# Radio_USB.net
KiCad netlist of a schematic drawn in Altium Designer
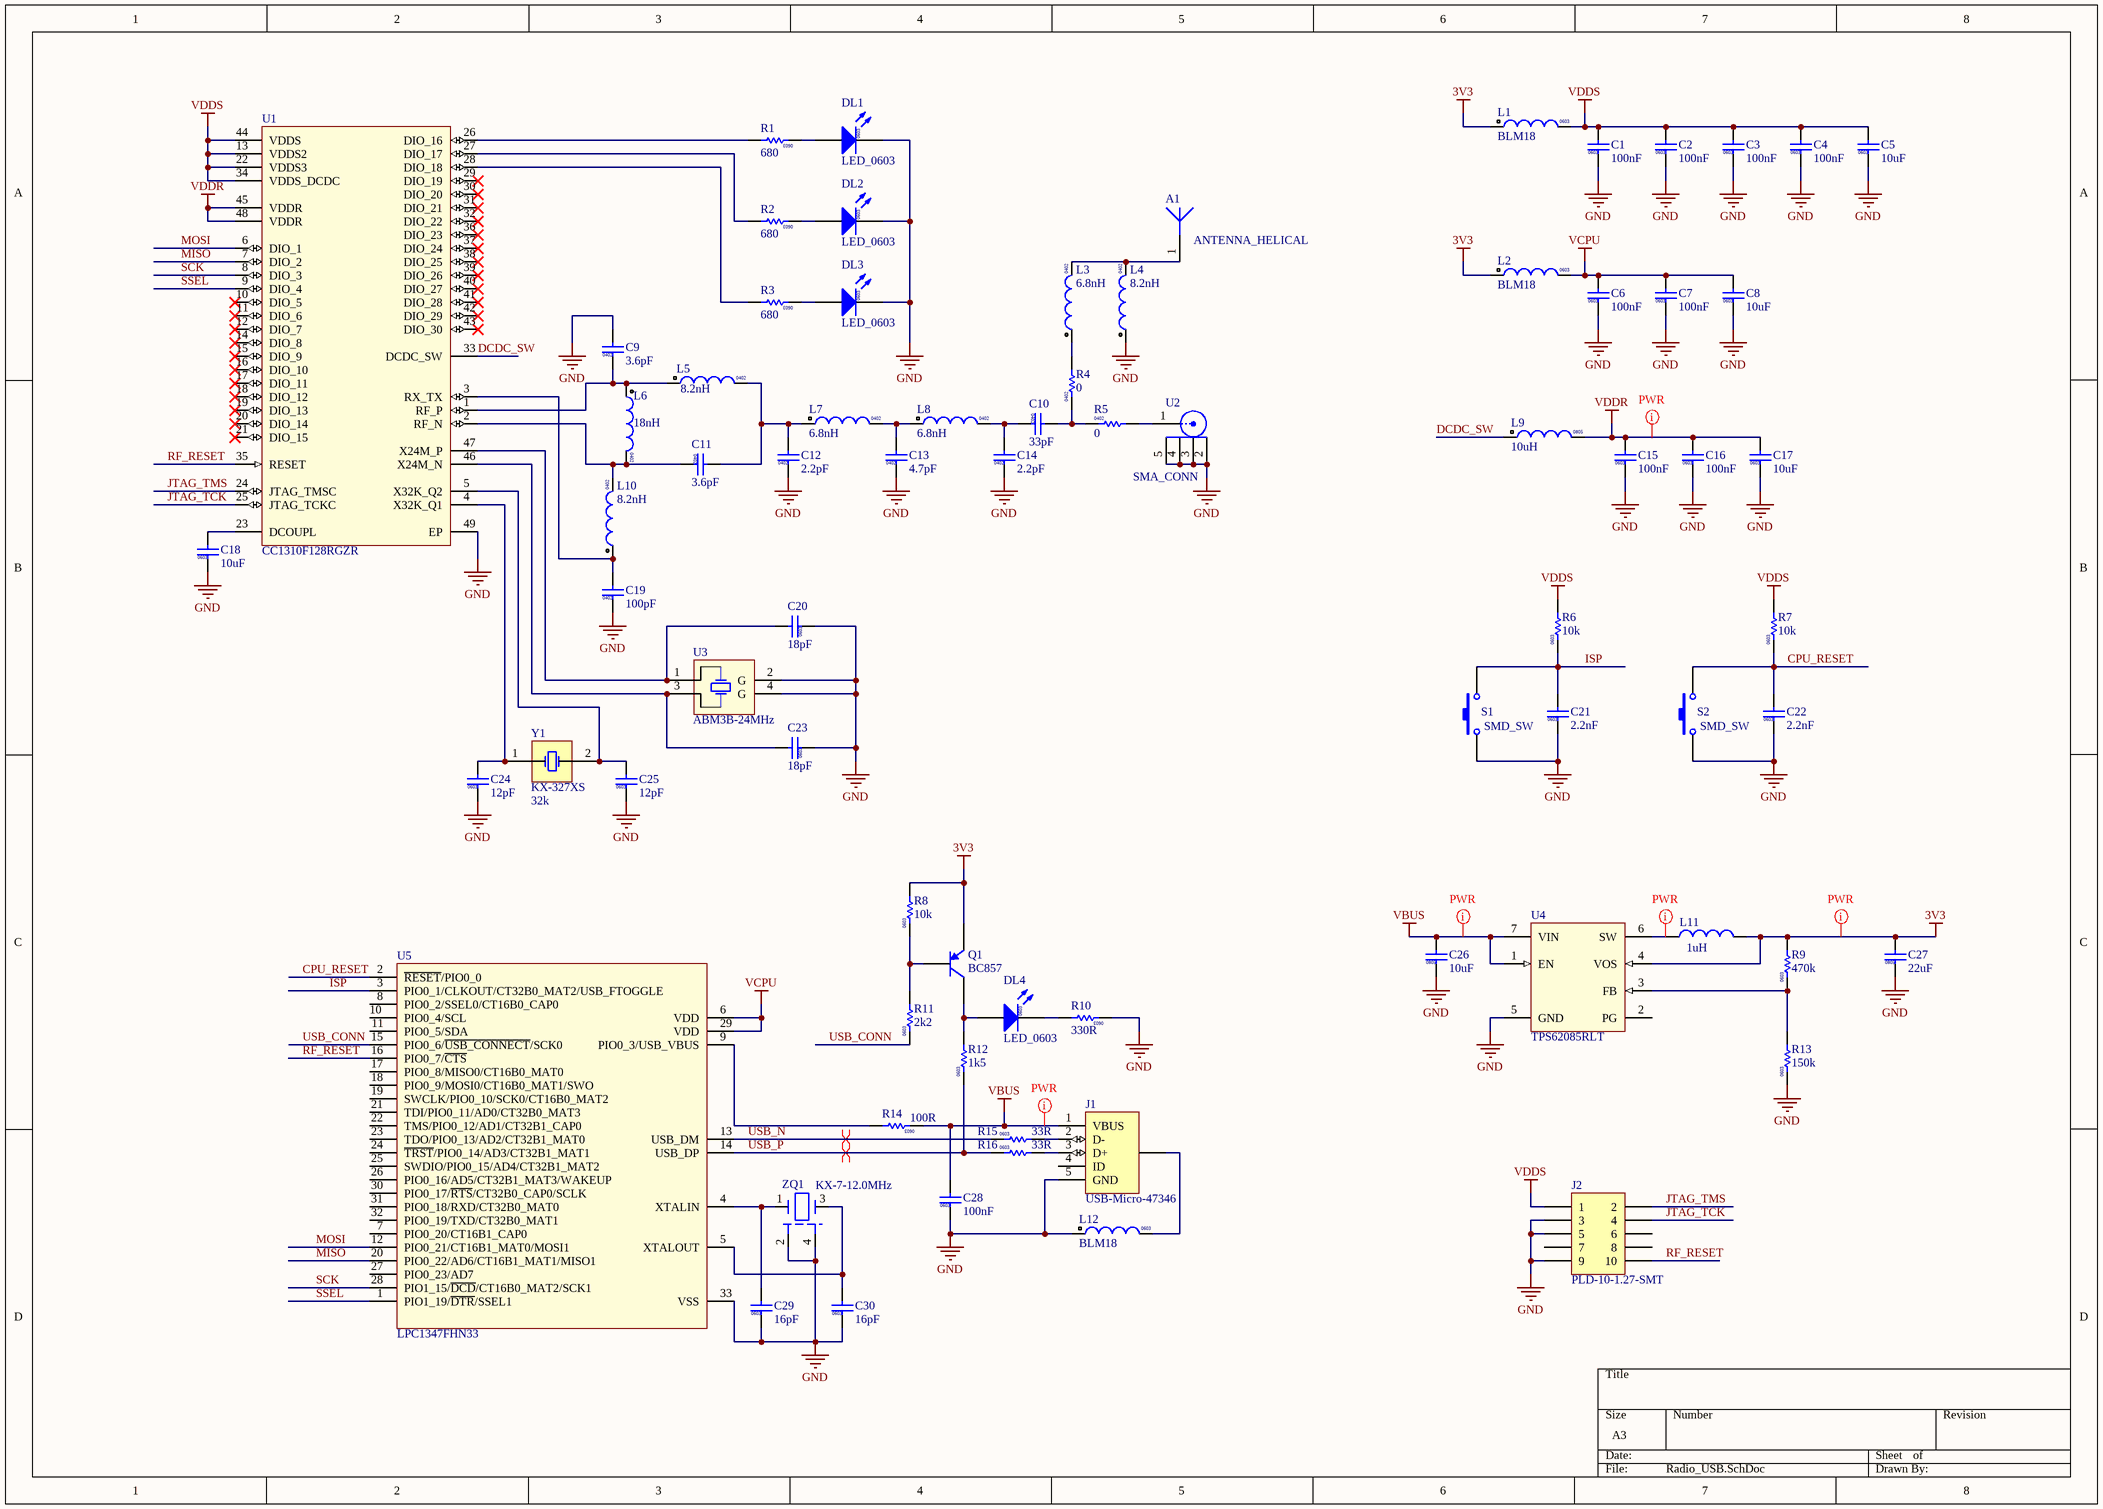
[diagram p0: Radio_USB.SchDoc]

(export (version "E")
  (design (tool "Eeschema 10.0.6"))
  (components
    (comp (ref "A1")
      (value "ANTENNA_HELICAL")
      (footprint "ANTENNA")
      (description "PCB helical antenna")
      (libsource (lib "Discrete") (part "ANTENNA_HELICAL"))
    )
    (comp (ref "C1")
      (value "100nF")
      (footprint "CAPC1608-0603M")
      (description "Capacitor 0603")
      (fields (field (name "Comment") "CAPC_0603"))
      (libsource (lib "Passive") (part "CAPC_0603"))
    )
    (comp (ref "C2")
      (value "100nF")
      (footprint "CAPC1608-0603M")
      (description "Capacitor 0603")
      (fields (field (name "Comment") "CAPC_0603"))
      (libsource (lib "Passive") (part "CAPC_0603"))
    )
    (comp (ref "C3")
      (value "100nF")
      (footprint "CAPC1608-0603M")
      (description "Capacitor 0603")
      (fields (field (name "Comment") "CAPC_0603"))
      (libsource (lib "Passive") (part "CAPC_0603"))
    )
    (comp (ref "C4")
      (value "100nF")
      (footprint "CAPC1608-0603M")
      (description "Capacitor 0603")
      (fields (field (name "Comment") "CAPC_0603"))
      (libsource (lib "Passive") (part "CAPC_0603"))
    )
    (comp (ref "C5")
      (value "10uF")
      (footprint "CAPC1608-0603M")
      (description "Capacitor 0603")
      (fields (field (name "Comment") "CAPC_0603"))
      (libsource (lib "Passive") (part "CAPC_0603"))
    )
    (comp (ref "C6")
      (value "100nF")
      (footprint "CAPC1608-0603M")
      (description "Capacitor 0603")
      (fields (field (name "Comment") "CAPC_0603"))
      (libsource (lib "Passive") (part "CAPC_0603"))
    )
    (comp (ref "C7")
      (value "100nF")
      (footprint "CAPC1608-0603M")
      (description "Capacitor 0603")
      (fields (field (name "Comment") "CAPC_0603"))
      (libsource (lib "Passive") (part "CAPC_0603"))
    )
    (comp (ref "C8")
      (value "10uF")
      (footprint "CAPC1608-0603M")
      (description "Capacitor 0603")
      (fields (field (name "Comment") "CAPC_0603"))
      (libsource (lib "Passive") (part "CAPC_0603"))
    )
    (comp (ref "C9")
      (value "3.6pF")
      (footprint "CAPC1005-0402M")
      (description "Capacitor 0402")
      (fields (field (name "Comment") "CAPC_0402"))
      (libsource (lib "Passive") (part "CAPC_0402"))
    )
    (comp (ref "C10")
      (value "33pF")
      (footprint "CAPC1005-0402M")
      (description "Capacitor 0402")
      (fields (field (name "Comment") "CAPC_0402"))
      (libsource (lib "Passive") (part "CAPC_0402"))
    )
    (comp (ref "C11")
      (value "3.6pF")
      (footprint "CAPC1005-0402M")
      (description "Capacitor 0402")
      (fields (field (name "Comment") "CAPC_0402"))
      (libsource (lib "Passive") (part "CAPC_0402"))
    )
    (comp (ref "C12")
      (value "2.2pF")
      (footprint "CAPC1005-0402M")
      (description "Capacitor 0402")
      (fields (field (name "Comment") "CAPC_0402"))
      (libsource (lib "Passive") (part "CAPC_0402"))
    )
    (comp (ref "C13")
      (value "4.7pF")
      (footprint "CAPC1005-0402M")
      (description "Capacitor 0402")
      (fields (field (name "Comment") "CAPC_0402"))
      (libsource (lib "Passive") (part "CAPC_0402"))
    )
    (comp (ref "C14")
      (value "2.2pF")
      (footprint "CAPC1005-0402M")
      (description "Capacitor 0402")
      (fields (field (name "Comment") "CAPC_0402"))
      (libsource (lib "Passive") (part "CAPC_0402"))
    )
    (comp (ref "C15")
      (value "100nF")
      (footprint "CAPC1608-0603M")
      (description "Capacitor 0603")
      (fields (field (name "Comment") "CAPC_0603"))
      (libsource (lib "Passive") (part "CAPC_0603"))
    )
    (comp (ref "C16")
      (value "100nF")
      (footprint "CAPC1608-0603M")
      (description "Capacitor 0603")
      (fields (field (name "Comment") "CAPC_0603"))
      (libsource (lib "Passive") (part "CAPC_0603"))
    )
    (comp (ref "C17")
      (value "10uF")
      (footprint "CAPC1608-0603M")
      (description "Capacitor 0603")
      (fields (field (name "Comment") "CAPC_0603"))
      (libsource (lib "Passive") (part "CAPC_0603"))
    )
    (comp (ref "C18")
      (value "10uF")
      (footprint "CAPC1608-0603M")
      (description "Capacitor 0603")
      (fields (field (name "Comment") "CAPC_0603"))
      (libsource (lib "Passive") (part "CAPC_0603"))
    )
    (comp (ref "C19")
      (value "100pF")
      (footprint "CAPC1005-0402M")
      (description "Capacitor 0402")
      (fields (field (name "Comment") "CAPC_0402"))
      (libsource (lib "Passive") (part "CAPC_0402"))
    )
    (comp (ref "C20")
      (value "18pF")
      (footprint "CAPC1608-0603M")
      (description "Capacitor 0603")
      (fields (field (name "Comment") "CAPC_0603"))
      (libsource (lib "Passive") (part "CAPC_0603"))
    )
    (comp (ref "C21")
      (value "2.2nF")
      (footprint "CAPC1608-0603M")
      (description "Capacitor 0603")
      (fields (field (name "Comment") "CAPC_0603"))
      (libsource (lib "Passive") (part "CAPC_0603"))
    )
    (comp (ref "C22")
      (value "2.2nF")
      (footprint "CAPC1608-0603M")
      (description "Capacitor 0603")
      (fields (field (name "Comment") "CAPC_0603"))
      (libsource (lib "Passive") (part "CAPC_0603"))
    )
    (comp (ref "C23")
      (value "18pF")
      (footprint "CAPC1608-0603M")
      (description "Capacitor 0603")
      (fields (field (name "Comment") "CAPC_0603"))
      (libsource (lib "Passive") (part "CAPC_0603"))
    )
    (comp (ref "C24")
      (value "12pF")
      (footprint "CAPC1608-0603M")
      (description "Capacitor 0603")
      (fields (field (name "Comment") "CAPC_0603"))
      (libsource (lib "Passive") (part "CAPC_0603"))
    )
    (comp (ref "C25")
      (value "12pF")
      (footprint "CAPC1608-0603M")
      (description "Capacitor 0603")
      (fields (field (name "Comment") "CAPC_0603"))
      (libsource (lib "Passive") (part "CAPC_0603"))
    )
    (comp (ref "C26")
      (value "10uF")
      (footprint "CAPC2012-0805M")
      (description "Capacitor 0805")
      (fields (field (name "Comment") "CAPC_0805"))
      (libsource (lib "Passive") (part "CAPC_0805"))
    )
    (comp (ref "C27")
      (value "22uF")
      (footprint "CAPC2012-0805M")
      (description "Capacitor 0805")
      (fields (field (name "Comment") "CAPC_0805"))
      (libsource (lib "Passive") (part "CAPC_0805"))
    )
    (comp (ref "C28")
      (value "100nF")
      (footprint "CAPC1608-0603M")
      (description "Capacitor 0603")
      (fields (field (name "Comment") "CAPC_0603"))
      (libsource (lib "Passive") (part "CAPC_0603"))
    )
    (comp (ref "C29")
      (value "16pF")
      (footprint "CAPC1608-0603M")
      (description "Capacitor 0603")
      (fields (field (name "Comment") "CAPC_0603"))
      (libsource (lib "Passive") (part "CAPC_0603"))
    )
    (comp (ref "C30")
      (value "16pF")
      (footprint "CAPC1608-0603M")
      (description "Capacitor 0603")
      (fields (field (name "Comment") "CAPC_0603"))
      (libsource (lib "Passive") (part "CAPC_0603"))
    )
    (comp (ref "DL1")
      (value "LED_0603")
      (footprint "DIODEC1608-0603")
      (description "LED 0603")
      (fields (field (name "PART NUMBER") "*BL-..."))
      (libsource (lib "Discrete") (part "LED_0603"))
    )
    (comp (ref "DL2")
      (value "LED_0603")
      (footprint "DIODEC1608-0603")
      (description "LED 0603")
      (fields (field (name "PART NUMBER") "*BL-..."))
      (libsource (lib "Discrete") (part "LED_0603"))
    )
    (comp (ref "DL3")
      (value "LED_0603")
      (footprint "DIODEC1608-0603")
      (description "LED 0603")
      (fields (field (name "PART NUMBER") "*BL-..."))
      (libsource (lib "Discrete") (part "LED_0603"))
    )
    (comp (ref "DL4")
      (value "LED_0603")
      (footprint "DIODEC1608-0603")
      (description "LED 0603")
      (fields (field (name "PART NUMBER") "*BL-..."))
      (libsource (lib "Discrete") (part "LED_0603"))
    )
    (comp (ref "J1")
      (value "USB-Micro-47346")
      (footprint "USB_micro_B")
      (description "Micro USB B Molex 47346")
      (libsource (lib "Connectors_dif") (part "USB-Micro-47346"))
    )
    (comp (ref "J2")
      (value "PLD-10-1.27-SMT")
      (footprint "PLD-10-1.27-SMT")
      (fields (field (name "PUBLISHER") "Altium Limited"))
      (libsource (lib "Connectors_dif") (part "PLD-10-1.27-SMT"))
    )
    (comp (ref "L1")
      (value "BLM18")
      (footprint "INDC1608M")
      (description "Chip Inductor, Body Body 1.6x0.8mm")
      (fields (field (name "Comment") "INDC-0603"))
      (libsource (lib "Passive") (part "INDC-0603"))
    )
    (comp (ref "L2")
      (value "BLM18")
      (footprint "INDC1608M")
      (description "Chip Inductor, Body Body 1.6x0.8mm")
      (fields (field (name "Comment") "INDC-0603"))
      (libsource (lib "Passive") (part "INDC-0603"))
    )
    (comp (ref "L3")
      (value "6.8nH")
      (footprint "INDC1005-0402-RF2.4GHz")
      (description "Chip Inductor, Body 1.0x0.5mm")
      (fields (field (name "Comment") "INDC-0402") (field (name "PUBLISHER") "Altium Limited"))
      (libsource (lib "Passive") (part "INDC-0402"))
    )
    (comp (ref "L4")
      (value "8.2nH")
      (footprint "INDC1005-0402-RF2.4GHz")
      (description "Chip Inductor, Body 1.0x0.5mm")
      (fields (field (name "Comment") "INDC-0402") (field (name "PUBLISHER") "Altium Limited"))
      (libsource (lib "Passive") (part "INDC-0402"))
    )
    (comp (ref "L5")
      (value "8.2nH")
      (footprint "INDC1005-0402-RF2.4GHz")
      (description "Chip Inductor, Body 1.0x0.5mm")
      (fields (field (name "Comment") "INDC-0402") (field (name "PUBLISHER") "Altium Limited"))
      (libsource (lib "") (part "INDC-0402_1"))
    )
    (comp (ref "L6")
      (value "18nH")
      (footprint "INDC1005-0402-RF2.4GHz")
      (description "Chip Inductor, Body 1.0x0.5mm")
      (fields (field (name "Comment") "INDC-0402") (field (name "PUBLISHER") "Altium Limited"))
      (libsource (lib "Passive") (part "INDC-0402"))
    )
    (comp (ref "L7")
      (value "6.8nH")
      (footprint "INDC1005-0402-RF2.4GHz")
      (description "Chip Inductor, Body 1.0x0.5mm")
      (fields (field (name "Comment") "INDC-0402") (field (name "PUBLISHER") "Altium Limited"))
      (libsource (lib "Passive") (part "INDC-0402"))
    )
    (comp (ref "L8")
      (value "6.8nH")
      (footprint "INDC1005-0402-RF2.4GHz")
      (description "Chip Inductor, Body 1.0x0.5mm")
      (fields (field (name "Comment") "INDC-0402") (field (name "PUBLISHER") "Altium Limited"))
      (libsource (lib "Passive") (part "INDC-0402"))
    )
    (comp (ref "L9")
      (value "10uH")
      (footprint "INDC2012M")
      (description "Chip Inductor, Body Body 2.0x1.2mm")
      (fields (field (name "Comment") "INDC-0805"))
      (libsource (lib "Passive") (part "INDC-0805"))
    )
    (comp (ref "L10")
      (value "8.2nH")
      (footprint "INDC1005-0402-RF2.4GHz")
      (description "Chip Inductor, Body 1.0x0.5mm")
      (fields (field (name "Comment") "INDC-0402") (field (name "PUBLISHER") "Altium Limited"))
      (libsource (lib "Passive") (part "INDC-0402"))
    )
    (comp (ref "L11")
      (value "1uH")
      (footprint "XFL4015")
      (description "Power Inductors")
      (fields (field (name "PARTNUMBER") "XFL4020-102MEC") (field (name "Comment") "XFL4015"))
      (libsource (lib "Passive") (part "XFL4015"))
    )
    (comp (ref "L12")
      (value "BLM18")
      (footprint "INDC1608M")
      (description "Chip Inductor, Body Body 1.6x0.8mm")
      (fields (field (name "Comment") "INDC-0603"))
      (libsource (lib "Passive") (part "INDC-0603"))
    )
    (comp (ref "Q1")
      (value "BC857")
      (footprint "SOT23-3M")
      (description "BC857 PNP Transistor")
      (libsource (lib "Discrete") (part "BC857"))
    )
    (comp (ref "R1")
      (value "680")
      (footprint "RESC1608-0603M")
      (description "Resistor 0603")
      (fields (field (name "Comment") "RESC_0603"))
      (libsource (lib "Passive") (part "RESC_0603"))
    )
    (comp (ref "R2")
      (value "680")
      (footprint "RESC1608-0603M")
      (description "Resistor 0603")
      (fields (field (name "Comment") "RESC_0603"))
      (libsource (lib "Passive") (part "RESC_0603"))
    )
    (comp (ref "R3")
      (value "680")
      (footprint "RESC1608-0603M")
      (description "Resistor 0603")
      (fields (field (name "Comment") "RESC_0603"))
      (libsource (lib "Passive") (part "RESC_0603"))
    )
    (comp (ref "R4")
      (value "0")
      (footprint "RESC1005-0402M")
      (description "Resistor 0402")
      (fields (field (name "Comment") "RESC_0402"))
      (libsource (lib "Passive") (part "RESC_0402"))
    )
    (comp (ref "R5")
      (value "0")
      (footprint "RESC1005-0402M")
      (description "Resistor 0402")
      (fields (field (name "Comment") "RESC_0402"))
      (libsource (lib "Passive") (part "RESC_0402"))
    )
    (comp (ref "R6")
      (value "10k")
      (footprint "RESC1608-0603M")
      (description "Resistor 0603")
      (fields (field (name "Comment") "RESC_0603"))
      (libsource (lib "Passive") (part "RESC_0603"))
    )
    (comp (ref "R7")
      (value "10k")
      (footprint "RESC1608-0603M")
      (description "Resistor 0603")
      (fields (field (name "Comment") "RESC_0603"))
      (libsource (lib "Passive") (part "RESC_0603"))
    )
    (comp (ref "R8")
      (value "10k")
      (footprint "RESC1608-0603M")
      (description "Resistor 0603")
      (fields (field (name "Comment") "RESC_0603"))
      (libsource (lib "Passive") (part "RESC_0603"))
    )
    (comp (ref "R9")
      (value "470k")
      (footprint "RESC1608-0603M")
      (description "Resistor 0603")
      (fields (field (name "Comment") "RESC_0603"))
      (libsource (lib "Passive") (part "RESC_0603"))
    )
    (comp (ref "R10")
      (value "330R")
      (footprint "RESC1608-0603M")
      (description "Resistor 0603")
      (fields (field (name "Comment") "RESC_0603"))
      (libsource (lib "Passive") (part "RESC_0603"))
    )
    (comp (ref "R11")
      (value "2k2")
      (footprint "RESC1608-0603M")
      (description "Resistor 0603")
      (fields (field (name "Comment") "RESC_0603"))
      (libsource (lib "Passive") (part "RESC_0603"))
    )
    (comp (ref "R12")
      (value "1k5")
      (footprint "RESC1608-0603M")
      (description "Resistor 0603")
      (fields (field (name "Comment") "RESC_0603"))
      (libsource (lib "Passive") (part "RESC_0603"))
    )
    (comp (ref "R13")
      (value "150k")
      (footprint "RESC1608-0603M")
      (description "Resistor 0603")
      (fields (field (name "Comment") "RESC_0603"))
      (libsource (lib "Passive") (part "RESC_0603"))
    )
    (comp (ref "R14")
      (value "100R")
      (footprint "RESC1608-0603M")
      (description "Resistor 0603")
      (fields (field (name "Comment") "RESC_0603"))
      (libsource (lib "Passive") (part "RESC_0603"))
    )
    (comp (ref "R15")
      (value "33R")
      (footprint "RESC1608-0603M")
      (description "Resistor 0603")
      (fields (field (name "Comment") "RESC_0603"))
      (libsource (lib "Passive") (part "RESC_0603"))
    )
    (comp (ref "R16")
      (value "33R")
      (footprint "RESC1608-0603M")
      (description "Resistor 0603")
      (fields (field (name "Comment") "RESC_0603"))
      (libsource (lib "Passive") (part "RESC_0603"))
    )
    (comp (ref "S1")
      (value "SMD_SW")
      (footprint "SMD_SW_1")
      (description "Switch")
      (fields (field (name "PUBLISHER") "Altium Limited"))
      (libsource (lib "General_Proj") (part "SMD_SW"))
    )
    (comp (ref "S2")
      (value "SMD_SW")
      (footprint "SMD_SW_1")
      (description "Switch")
      (fields (field (name "PUBLISHER") "Altium Limited"))
      (libsource (lib "General_Proj") (part "SMD_SW"))
    )
    (comp (ref "U1")
      (value "CC1310F128RGZR")
      (footprint "QFN-48M")
      (description "Ultralow Power Sub-1-GHz Wireless MCU")
      (libsource (lib "Analog_IC") (part "CC1310F128RGZR"))
    )
    (comp (ref "U2")
      (value "SMA_CONN")
      (footprint "SMA_CONN")
      (description "SMA Straight PCB Socket")
      (libsource (lib "RCMG") (part "SMA_CONN"))
    )
    (comp (ref "U3")
      (value "ABM3B-24MHz")
      (footprint "ABM3B-24MHz")
      (description "Crystal Oscillator, 24 MHz, SMD, 5mm x 3.2mm")
      (libsource (lib "Passive") (part "ABM3B-24MHz"))
    )
    (comp (ref "U4")
      (value "TPS62085RLT")
      (footprint "RLT7-0506")
      (description "Step-Down Converter With Hiccup Short-Circuit Protection, 2.5-V to 6.0-V input Voltage Range")
      (libsource (lib "Analog_IC") (part "TPS62085RLT"))
    )
    (comp (ref "U5")
      (value "LPC1347FHN33")
      (footprint "HVQFN33_L")
      (description "NXP 32-bit ARM Cortex-M3")
      (libsource (lib "RCMG") (part "LPC1347FHN33"))
    )
    (comp (ref "Y1")
      (value "KX-327XS")
      (footprint "KX-327xs")
      (description "Surface Mount Quartz Crystal")
      (fields (field (name "ALTIUM_VALUE") "32k"))
      (libsource (lib "Passive") (part "KX-327XS"))
    )
    (comp (ref "ZQ1")
      (value "KX-7-12.0MHz")
      (footprint "QRZ3.2x2.5")
      (description "Quartz SMD 3.2*2.5 mm body 4 pads")
      (fields (field (name "Comment") "QRZ3.2x2.5"))
      (libsource (lib "Passive") (part "QRZ3.2x2.5"))
    )
  )
  (nets
    (net (code "1") (name "/CPU_RESET") (class "Default")
      (node (ref "C22") (pin "2") (pinfunction "2_2") (pintype "passive"))
      (node (ref "R7") (pin "1") (pinfunction "1_1") (pintype "passive"))
      (node (ref "S2") (pin "2") (pinfunction "2_2") (pintype "passive"))
      (node (ref "U5") (pin "2") (pinfunction "~{RESET}/PIO0_0_2") (pintype "passive"))
    )
    (net (code "2") (name "/DCDC_SW") (class "Default")
      (node (ref "L9") (pin "1") (pinfunction "1_1") (pintype "passive"))
      (node (ref "U1") (pin "33") (pinfunction "DCDC_SW_33") (pintype "power_in"))
    )
    (net (code "3") (name "/ISP") (class "Default")
      (node (ref "C21") (pin "2") (pinfunction "2_2") (pintype "passive"))
      (node (ref "R6") (pin "1") (pinfunction "1_1") (pintype "passive"))
      (node (ref "S1") (pin "2") (pinfunction "2_2") (pintype "passive"))
      (node (ref "U5") (pin "3") (pinfunction "PIO0_1/CLKOUT/CT32B0_MAT2/USB_FTOGGLE_3") (pintype "passive"))
    )
    (net (code "4") (name "/JTAG_TCK") (class "Default")
      (node (ref "J2") (pin "4") (pinfunction "4_4") (pintype "passive"))
      (node (ref "U1") (pin "25") (pinfunction "JTAG_TCKC_25") (pintype "bidirectional"))
    )
    (net (code "5") (name "/JTAG_TMS") (class "Default")
      (node (ref "J2") (pin "2") (pinfunction "2_2") (pintype "passive"))
      (node (ref "U1") (pin "24") (pinfunction "JTAG_TMSC_24") (pintype "bidirectional"))
    )
    (net (code "6") (name "/MISO") (class "Default")
      (node (ref "U1") (pin "7") (pinfunction "DIO_2_7") (pintype "bidirectional"))
      (node (ref "U5") (pin "20") (pinfunction "PIO0_22/AD6/CT16B1_MAT1/MISO1_20") (pintype "passive"))
    )
    (net (code "7") (name "/MOSI") (class "Default")
      (node (ref "U1") (pin "6") (pinfunction "DIO_1_6") (pintype "bidirectional"))
      (node (ref "U5") (pin "12") (pinfunction "PIO0_21/CT16B1_MAT0/MOSI1_12") (pintype "passive"))
    )
    (net (code "8") (name "/RF_RESET") (class "Default")
      (node (ref "J2") (pin "10") (pinfunction "10_10") (pintype "passive"))
      (node (ref "U1") (pin "35") (pinfunction "RESET_35") (pintype "input"))
      (node (ref "U5") (pin "16") (pinfunction "PIO0_7/~{CTS}_16") (pintype "passive"))
    )
    (net (code "9") (name "/SCK") (class "Default")
      (node (ref "U1") (pin "8") (pinfunction "DIO_3_8") (pintype "bidirectional"))
      (node (ref "U5") (pin "28") (pinfunction "PIO1_15/~{DCD}/CT16B0_MAT2/SCK1_28") (pintype "passive"))
    )
    (net (code "10") (name "/SSEL") (class "Default")
      (node (ref "U1") (pin "9") (pinfunction "DIO_4_9") (pintype "bidirectional"))
      (node (ref "U5") (pin "1") (pinfunction "PIO1_19/~{DTR}/SSEL1_1") (pintype "passive"))
    )
    (net (code "11") (name "/USB_CONN") (class "Default")
      (node (ref "R11") (pin "1") (pinfunction "1_1") (pintype "passive"))
      (node (ref "U5") (pin "15") (pinfunction "PIO0_6/~{USB_CONNECT}/SCK0_15") (pintype "passive"))
    )
    (net (code "12") (name "/USB_N") (class "Default")
      (node (ref "R15") (pin "1") (pinfunction "1_1") (pintype "passive"))
      (node (ref "U5") (pin "13") (pinfunction "USB_DM_13") (pintype "passive"))
    )
    (net (code "13") (name "/USB_P") (class "Default")
      (node (ref "R12") (pin "1") (pinfunction "1_1") (pintype "passive"))
      (node (ref "R16") (pin "1") (pinfunction "1_1") (pintype "passive"))
      (node (ref "U5") (pin "14") (pinfunction "USB_DP_14") (pintype "passive"))
    )
    (net (code "14") (name "3V3") (class "Default")
      (node (ref "C27") (pin "2") (pinfunction "2_2") (pintype "passive"))
      (node (ref "L1") (pin "1") (pinfunction "1_1") (pintype "passive"))
      (node (ref "L11") (pin "2") (pinfunction "2_2") (pintype "passive"))
      (node (ref "L2") (pin "1") (pinfunction "1_1") (pintype "passive"))
      (node (ref "Q1") (pin "2") (pinfunction "E_2") (pintype "passive"))
      (node (ref "R8") (pin "2") (pinfunction "2_2") (pintype "passive"))
      (node (ref "R9") (pin "2") (pinfunction "2_2") (pintype "passive"))
      (node (ref "U4") (pin "4") (pinfunction "VOS_4") (pintype "input"))
    )
    (net (code "15") (name "GND") (class "Default")
      (node (ref "C1") (pin "1") (pinfunction "1_1") (pintype "passive"))
      (node (ref "C12") (pin "1") (pinfunction "1_1") (pintype "passive"))
      (node (ref "C13") (pin "1") (pinfunction "1_1") (pintype "passive"))
      (node (ref "C14") (pin "1") (pinfunction "1_1") (pintype "passive"))
      (node (ref "C15") (pin "1") (pinfunction "1_1") (pintype "passive"))
      (node (ref "C16") (pin "1") (pinfunction "1_1") (pintype "passive"))
      (node (ref "C17") (pin "1") (pinfunction "1_1") (pintype "passive"))
      (node (ref "C18") (pin "1") (pinfunction "1_1") (pintype "passive"))
      (node (ref "C19") (pin "1") (pinfunction "1_1") (pintype "passive"))
      (node (ref "C2") (pin "1") (pinfunction "1_1") (pintype "passive"))
      (node (ref "C20") (pin "1") (pinfunction "1_1") (pintype "passive"))
      (node (ref "C21") (pin "1") (pinfunction "1_1") (pintype "passive"))
      (node (ref "C22") (pin "1") (pinfunction "1_1") (pintype "passive"))
      (node (ref "C23") (pin "1") (pinfunction "1_1") (pintype "passive"))
      (node (ref "C24") (pin "1") (pinfunction "1_1") (pintype "passive"))
      (node (ref "C25") (pin "1") (pinfunction "1_1") (pintype "passive"))
      (node (ref "C26") (pin "1") (pinfunction "1_1") (pintype "passive"))
      (node (ref "C27") (pin "1") (pinfunction "1_1") (pintype "passive"))
      (node (ref "C28") (pin "1") (pinfunction "1_1") (pintype "passive"))
      (node (ref "C29") (pin "1") (pinfunction "1_1") (pintype "passive"))
      (node (ref "C3") (pin "1") (pinfunction "1_1") (pintype "passive"))
      (node (ref "C30") (pin "1") (pinfunction "1_1") (pintype "passive"))
      (node (ref "C4") (pin "1") (pinfunction "1_1") (pintype "passive"))
      (node (ref "C5") (pin "1") (pinfunction "1_1") (pintype "passive"))
      (node (ref "C6") (pin "1") (pinfunction "1_1") (pintype "passive"))
      (node (ref "C7") (pin "1") (pinfunction "1_1") (pintype "passive"))
      (node (ref "C8") (pin "1") (pinfunction "1_1") (pintype "passive"))
      (node (ref "C9") (pin "2") (pinfunction "2_2") (pintype "passive"))
      (node (ref "DL1") (pin "2") (pinfunction "K_2") (pintype "passive"))
      (node (ref "DL2") (pin "2") (pinfunction "K_2") (pintype "passive"))
      (node (ref "DL3") (pin "2") (pinfunction "K_2") (pintype "passive"))
      (node (ref "J1") (pin "5") (pinfunction "GND_5") (pintype "power_in"))
      (node (ref "J2") (pin "3") (pinfunction "3_3") (pintype "passive"))
      (node (ref "J2") (pin "5") (pinfunction "5_5") (pintype "passive"))
      (node (ref "J2") (pin "9") (pinfunction "9_9") (pintype "passive"))
      (node (ref "L12") (pin "1") (pinfunction "1_1") (pintype "passive"))
      (node (ref "L4") (pin "1") (pinfunction "1_1") (pintype "passive"))
      (node (ref "R10") (pin "1") (pinfunction "1_1") (pintype "passive"))
      (node (ref "R13") (pin "1") (pinfunction "1_1") (pintype "passive"))
      (node (ref "S1") (pin "1") (pinfunction "1_1") (pintype "passive"))
      (node (ref "S2") (pin "1") (pinfunction "1_1") (pintype "passive"))
      (node (ref "U1") (pin "49") (pinfunction "EP_49") (pintype "power_in"))
      (node (ref "U2") (pin "2") (pinfunction "2_2") (pintype "passive"))
      (node (ref "U2") (pin "3") (pinfunction "3_3") (pintype "passive"))
      (node (ref "U2") (pin "4") (pinfunction "4_4") (pintype "passive"))
      (node (ref "U2") (pin "5") (pinfunction "5_5") (pintype "passive"))
      (node (ref "U3") (pin "2") (pinfunction "G_2") (pintype "power_in"))
      (node (ref "U3") (pin "4") (pinfunction "G_4") (pintype "power_in"))
      (node (ref "U4") (pin "5") (pinfunction "GND_5") (pintype "power_in"))
      (node (ref "U5") (pin "33") (pinfunction "VSS_33") (pintype "passive"))
      (node (ref "ZQ1") (pin "2") (pinfunction "2_2") (pintype "passive"))
      (node (ref "ZQ1") (pin "4") (pinfunction "4_4") (pintype "passive"))
    )
    (net (code "16") (name "Net-(A1-Pad1)") (class "Default")
      (node (ref "A1") (pin "1") (pinfunction "1_1") (pintype "passive"))
      (node (ref "L3") (pin "2") (pinfunction "2_2") (pintype "passive"))
      (node (ref "L4") (pin "2") (pinfunction "2_2") (pintype "passive"))
    )
    (net (code "17") (name "Net-(C10-Pad1)") (class "Default")
      (node (ref "C10") (pin "1") (pinfunction "1_1") (pintype "passive"))
      (node (ref "C14") (pin "2") (pinfunction "2_2") (pintype "passive"))
      (node (ref "L8") (pin "2") (pinfunction "2_2") (pintype "passive"))
    )
    (net (code "18") (name "Net-(C10-Pad2)") (class "Default")
      (node (ref "C10") (pin "2") (pinfunction "2_2") (pintype "passive"))
      (node (ref "R4") (pin "1") (pinfunction "1_1") (pintype "passive"))
      (node (ref "R5") (pin "1") (pinfunction "1_1") (pintype "passive"))
    )
    (net (code "19") (name "Net-(C11-Pad2)") (class "Default")
      (node (ref "C11") (pin "2") (pinfunction "2_2") (pintype "passive"))
      (node (ref "C12") (pin "2") (pinfunction "2_2") (pintype "passive"))
      (node (ref "L5") (pin "2") (pinfunction "2_2") (pintype "passive"))
      (node (ref "L7") (pin "1") (pinfunction "1_1") (pintype "passive"))
    )
    (net (code "20") (name "Net-(C13-Pad2)") (class "Default")
      (node (ref "C13") (pin "2") (pinfunction "2_2") (pintype "passive"))
      (node (ref "L7") (pin "2") (pinfunction "2_2") (pintype "passive"))
      (node (ref "L8") (pin "1") (pinfunction "1_1") (pintype "passive"))
    )
    (net (code "21") (name "Net-(DL1-A)") (class "Default")
      (node (ref "DL1") (pin "1") (pinfunction "A_1") (pintype "passive"))
      (node (ref "R1") (pin "1") (pinfunction "1_1") (pintype "passive"))
    )
    (net (code "22") (name "Net-(DL2-A)") (class "Default")
      (node (ref "DL2") (pin "1") (pinfunction "A_1") (pintype "passive"))
      (node (ref "R2") (pin "1") (pinfunction "1_1") (pintype "passive"))
    )
    (net (code "23") (name "Net-(DL3-A)") (class "Default")
      (node (ref "DL3") (pin "1") (pinfunction "A_1") (pintype "passive"))
      (node (ref "R3") (pin "1") (pinfunction "1_1") (pintype "passive"))
    )
    (net (code "24") (name "Net-(DL4-A)") (class "Default")
      (node (ref "DL4") (pin "1") (pinfunction "A_1") (pintype "passive"))
      (node (ref "Q1") (pin "3") (pinfunction "C_3") (pintype "passive"))
      (node (ref "R12") (pin "2") (pinfunction "2_2") (pintype "passive"))
    )
    (net (code "25") (name "Net-(DL4-K)") (class "Default")
      (node (ref "DL4") (pin "2") (pinfunction "K_2") (pintype "passive"))
      (node (ref "R10") (pin "2") (pinfunction "2_2") (pintype "passive"))
    )
    (net (code "26") (name "Net-(J1-D+)") (class "Default")
      (node (ref "J1") (pin "3") (pinfunction "D+_3") (pintype "bidirectional"))
      (node (ref "R16") (pin "2") (pinfunction "2_2") (pintype "passive"))
    )
    (net (code "27") (name "Net-(J1-D-)") (class "Default")
      (node (ref "J1") (pin "2") (pinfunction "D-_2") (pintype "bidirectional"))
      (node (ref "R15") (pin "2") (pinfunction "2_2") (pintype "passive"))
    )
    (net (code "28") (name "Net-(J1-SHLD)") (class "Default")
      (node (ref "J1") (pin "SHIELD") (pinfunction "SHLD_SHIELD") (pintype "passive"))
      (node (ref "L12") (pin "2") (pinfunction "2_2") (pintype "passive"))
    )
    (net (code "29") (name "Net-(L3-Pad1)") (class "Default")
      (node (ref "L3") (pin "1") (pinfunction "1_1") (pintype "passive"))
      (node (ref "R4") (pin "2") (pinfunction "2_2") (pintype "passive"))
    )
    (net (code "30") (name "Net-(Q1-B)") (class "Default")
      (node (ref "Q1") (pin "1") (pinfunction "B_1") (pintype "passive"))
      (node (ref "R11") (pin "2") (pinfunction "2_2") (pintype "passive"))
      (node (ref "R8") (pin "1") (pinfunction "1_1") (pintype "passive"))
    )
    (net (code "31") (name "Net-(R5-Pad2)") (class "Default")
      (node (ref "R5") (pin "2") (pinfunction "2_2") (pintype "passive"))
      (node (ref "U2") (pin "1") (pinfunction "1_1") (pintype "passive"))
    )
    (net (code "32") (name "Net-(U1-DCOUPL)") (class "Default")
      (node (ref "C18") (pin "2") (pinfunction "2_2") (pintype "passive"))
      (node (ref "U1") (pin "23") (pinfunction "DCOUPL_23") (pintype "passive"))
    )
    (net (code "33") (name "Net-(U1-DIO_16)") (class "Default")
      (node (ref "R1") (pin "2") (pinfunction "2_2") (pintype "passive"))
      (node (ref "U1") (pin "26") (pinfunction "DIO_16_26") (pintype "bidirectional"))
    )
    (net (code "34") (name "Net-(U1-DIO_17)") (class "Default")
      (node (ref "R2") (pin "2") (pinfunction "2_2") (pintype "passive"))
      (node (ref "U1") (pin "27") (pinfunction "DIO_17_27") (pintype "bidirectional"))
    )
    (net (code "35") (name "Net-(U1-DIO_18)") (class "Default")
      (node (ref "R3") (pin "2") (pinfunction "2_2") (pintype "passive"))
      (node (ref "U1") (pin "28") (pinfunction "DIO_18_28") (pintype "bidirectional"))
    )
    (net (code "36") (name "Net-(U1-RF_N)") (class "Default")
      (node (ref "C11") (pin "1") (pinfunction "1_1") (pintype "passive"))
      (node (ref "L10") (pin "2") (pinfunction "2_2") (pintype "passive"))
      (node (ref "L6") (pin "2") (pinfunction "2_2") (pintype "passive"))
      (node (ref "U1") (pin "2") (pinfunction "RF_N_2") (pintype "bidirectional"))
    )
    (net (code "37") (name "Net-(U1-RF_P)") (class "Default")
      (node (ref "C9") (pin "1") (pinfunction "1_1") (pintype "passive"))
      (node (ref "L5") (pin "1") (pinfunction "1_1") (pintype "passive"))
      (node (ref "L6") (pin "1") (pinfunction "1_1") (pintype "passive"))
      (node (ref "U1") (pin "1") (pinfunction "RF_P_1") (pintype "bidirectional"))
    )
    (net (code "38") (name "Net-(U1-RX_TX)") (class "Default")
      (node (ref "C19") (pin "2") (pinfunction "2_2") (pintype "passive"))
      (node (ref "L10") (pin "1") (pinfunction "1_1") (pintype "passive"))
      (node (ref "U1") (pin "3") (pinfunction "RX_TX_3") (pintype "bidirectional"))
    )
    (net (code "39") (name "Net-(U1-X24M_N)") (class "Default")
      (node (ref "C23") (pin "2") (pinfunction "2_2") (pintype "passive"))
      (node (ref "U1") (pin "46") (pinfunction "X24M_N_46") (pintype "passive"))
      (node (ref "U3") (pin "3") (pinfunction "3_3") (pintype "passive"))
    )
    (net (code "40") (name "Net-(U1-X24M_P)") (class "Default")
      (node (ref "C20") (pin "2") (pinfunction "2_2") (pintype "passive"))
      (node (ref "U1") (pin "47") (pinfunction "X24M_P_47") (pintype "passive"))
      (node (ref "U3") (pin "1") (pinfunction "1_1") (pintype "passive"))
    )
    (net (code "41") (name "Net-(U1-X32K_Q1)") (class "Default")
      (node (ref "C24") (pin "2") (pinfunction "2_2") (pintype "passive"))
      (node (ref "U1") (pin "4") (pinfunction "X32K_Q1_4") (pintype "passive"))
      (node (ref "Y1") (pin "1") (pintype "passive"))
    )
    (net (code "42") (name "Net-(U1-X32K_Q2)") (class "Default")
      (node (ref "C25") (pin "2") (pinfunction "2_2") (pintype "passive"))
      (node (ref "U1") (pin "5") (pinfunction "X32K_Q2_5") (pintype "passive"))
      (node (ref "Y1") (pin "2") (pintype "passive"))
    )
    (net (code "43") (name "Net-(U4-FB)") (class "Default")
      (node (ref "R13") (pin "2") (pinfunction "2_2") (pintype "passive"))
      (node (ref "R9") (pin "1") (pinfunction "1_1") (pintype "passive"))
      (node (ref "U4") (pin "3") (pinfunction "FB_3") (pintype "input"))
    )
    (net (code "44") (name "Net-(U4-SW)") (class "Default")
      (node (ref "L11") (pin "1") (pinfunction "1_1") (pintype "passive"))
      (node (ref "U4") (pin "6") (pinfunction "SW_6") (pintype "power_in"))
    )
    (net (code "45") (name "Net-(U5-PIO0_3{slash}USB_VBUS)") (class "Default")
      (node (ref "R14") (pin "2") (pinfunction "2_2") (pintype "passive"))
      (node (ref "U5") (pin "9") (pinfunction "PIO0_3/USB_VBUS_9") (pintype "passive"))
    )
    (net (code "46") (name "Net-(U5-XTALIN)") (class "Default")
      (node (ref "C29") (pin "2") (pinfunction "2_2") (pintype "passive"))
      (node (ref "U5") (pin "4") (pinfunction "XTALIN_4") (pintype "passive"))
      (node (ref "ZQ1") (pin "1") (pinfunction "1_1") (pintype "passive"))
    )
    (net (code "47") (name "Net-(U5-XTALOUT)") (class "Default")
      (node (ref "C30") (pin "2") (pinfunction "2_2") (pintype "passive"))
      (node (ref "U5") (pin "5") (pinfunction "XTALOUT_5") (pintype "passive"))
      (node (ref "ZQ1") (pin "3") (pinfunction "3_3") (pintype "passive"))
    )
    (net (code "48") (name "VBUS") (class "Default")
      (node (ref "C26") (pin "2") (pinfunction "2_2") (pintype "passive"))
      (node (ref "C28") (pin "2") (pinfunction "2_2") (pintype "passive"))
      (node (ref "J1") (pin "1") (pinfunction "VBUS_1") (pintype "power_in"))
      (node (ref "R14") (pin "1") (pinfunction "1_1") (pintype "passive"))
      (node (ref "U4") (pin "1") (pinfunction "EN_1") (pintype "input"))
      (node (ref "U4") (pin "7") (pinfunction "VIN_7") (pintype "power_in"))
    )
    (net (code "49") (name "VCPU") (class "Default")
      (node (ref "C6") (pin "2") (pinfunction "2_2") (pintype "passive"))
      (node (ref "C7") (pin "2") (pinfunction "2_2") (pintype "passive"))
      (node (ref "C8") (pin "2") (pinfunction "2_2") (pintype "passive"))
      (node (ref "L2") (pin "2") (pinfunction "2_2") (pintype "passive"))
      (node (ref "U5") (pin "29") (pinfunction "VDD_29") (pintype "passive"))
      (node (ref "U5") (pin "6") (pinfunction "VDD_6") (pintype "passive"))
    )
    (net (code "50") (name "VDDR") (class "Default")
      (node (ref "C15") (pin "2") (pinfunction "2_2") (pintype "passive"))
      (node (ref "C16") (pin "2") (pinfunction "2_2") (pintype "passive"))
      (node (ref "C17") (pin "2") (pinfunction "2_2") (pintype "passive"))
      (node (ref "L9") (pin "2") (pinfunction "2_2") (pintype "passive"))
      (node (ref "U1") (pin "45") (pinfunction "VDDR_45") (pintype "power_in"))
      (node (ref "U1") (pin "48") (pinfunction "VDDR_48") (pintype "power_in"))
    )
    (net (code "51") (name "VDDS") (class "Default")
      (node (ref "C1") (pin "2") (pinfunction "2_2") (pintype "passive"))
      (node (ref "C2") (pin "2") (pinfunction "2_2") (pintype "passive"))
      (node (ref "C3") (pin "2") (pinfunction "2_2") (pintype "passive"))
      (node (ref "C4") (pin "2") (pinfunction "2_2") (pintype "passive"))
      (node (ref "C5") (pin "2") (pinfunction "2_2") (pintype "passive"))
      (node (ref "J2") (pin "1") (pinfunction "1_1") (pintype "passive"))
      (node (ref "L1") (pin "2") (pinfunction "2_2") (pintype "passive"))
      (node (ref "R6") (pin "2") (pinfunction "2_2") (pintype "passive"))
      (node (ref "R7") (pin "2") (pinfunction "2_2") (pintype "passive"))
      (node (ref "U1") (pin "13") (pinfunction "VDDS2_13") (pintype "power_in"))
      (node (ref "U1") (pin "22") (pinfunction "VDDS3_22") (pintype "power_in"))
      (node (ref "U1") (pin "34") (pinfunction "VDDS_DCDC_34") (pintype "power_in"))
      (node (ref "U1") (pin "44") (pinfunction "VDDS_44") (pintype "power_in"))
    )
    (net (code "52") (name "unconnected-(J1-ID-Pad4)") (class "Default")
      (node (ref "J1") (pin "4") (pinfunction "ID_4") (pintype "passive"))
    )
    (net (code "53") (name "unconnected-(J2-Pad6)") (class "Default")
      (node (ref "J2") (pin "6") (pinfunction "6_6") (pintype "passive"))
    )
    (net (code "54") (name "unconnected-(J2-Pad7)") (class "Default")
      (node (ref "J2") (pin "7") (pinfunction "7_7") (pintype "passive"))
    )
    (net (code "55") (name "unconnected-(J2-Pad8)") (class "Default")
      (node (ref "J2") (pin "8") (pinfunction "8_8") (pintype "passive"))
    )
    (net (code "56") (name "unconnected-(U1-DIO_5-Pad10)") (class "Default")
      (node (ref "U1") (pin "10") (pinfunction "DIO_5_10") (pintype "bidirectional+no_connect"))
    )
    (net (code "57") (name "unconnected-(U1-DIO_6-Pad11)") (class "Default")
      (node (ref "U1") (pin "11") (pinfunction "DIO_6_11") (pintype "bidirectional+no_connect"))
    )
    (net (code "58") (name "unconnected-(U1-DIO_7-Pad12)") (class "Default")
      (node (ref "U1") (pin "12") (pinfunction "DIO_7_12") (pintype "bidirectional+no_connect"))
    )
    (net (code "59") (name "unconnected-(U1-DIO_8-Pad14)") (class "Default")
      (node (ref "U1") (pin "14") (pinfunction "DIO_8_14") (pintype "bidirectional+no_connect"))
    )
    (net (code "60") (name "unconnected-(U1-DIO_9-Pad15)") (class "Default")
      (node (ref "U1") (pin "15") (pinfunction "DIO_9_15") (pintype "bidirectional+no_connect"))
    )
    (net (code "61") (name "unconnected-(U1-DIO_10-Pad16)") (class "Default")
      (node (ref "U1") (pin "16") (pinfunction "DIO_10_16") (pintype "bidirectional+no_connect"))
    )
    (net (code "62") (name "unconnected-(U1-DIO_11-Pad17)") (class "Default")
      (node (ref "U1") (pin "17") (pinfunction "DIO_11_17") (pintype "bidirectional+no_connect"))
    )
    (net (code "63") (name "unconnected-(U1-DIO_12-Pad18)") (class "Default")
      (node (ref "U1") (pin "18") (pinfunction "DIO_12_18") (pintype "bidirectional+no_connect"))
    )
    (net (code "64") (name "unconnected-(U1-DIO_13-Pad19)") (class "Default")
      (node (ref "U1") (pin "19") (pinfunction "DIO_13_19") (pintype "bidirectional+no_connect"))
    )
    (net (code "65") (name "unconnected-(U1-DIO_14-Pad20)") (class "Default")
      (node (ref "U1") (pin "20") (pinfunction "DIO_14_20") (pintype "bidirectional+no_connect"))
    )
    (net (code "66") (name "unconnected-(U1-DIO_15-Pad21)") (class "Default")
      (node (ref "U1") (pin "21") (pinfunction "DIO_15_21") (pintype "bidirectional+no_connect"))
    )
    (net (code "67") (name "unconnected-(U1-DIO_19-Pad29)") (class "Default")
      (node (ref "U1") (pin "29") (pinfunction "DIO_19_29") (pintype "bidirectional+no_connect"))
    )
    (net (code "68") (name "unconnected-(U1-DIO_20-Pad30)") (class "Default")
      (node (ref "U1") (pin "30") (pinfunction "DIO_20_30") (pintype "bidirectional+no_connect"))
    )
    (net (code "69") (name "unconnected-(U1-DIO_21-Pad31)") (class "Default")
      (node (ref "U1") (pin "31") (pinfunction "DIO_21_31") (pintype "bidirectional+no_connect"))
    )
    (net (code "70") (name "unconnected-(U1-DIO_22-Pad32)") (class "Default")
      (node (ref "U1") (pin "32") (pinfunction "DIO_22_32") (pintype "bidirectional+no_connect"))
    )
    (net (code "71") (name "unconnected-(U1-DIO_23-Pad36)") (class "Default")
      (node (ref "U1") (pin "36") (pinfunction "DIO_23_36") (pintype "bidirectional+no_connect"))
    )
    (net (code "72") (name "unconnected-(U1-DIO_24-Pad37)") (class "Default")
      (node (ref "U1") (pin "37") (pinfunction "DIO_24_37") (pintype "bidirectional+no_connect"))
    )
    (net (code "73") (name "unconnected-(U1-DIO_25-Pad38)") (class "Default")
      (node (ref "U1") (pin "38") (pinfunction "DIO_25_38") (pintype "bidirectional+no_connect"))
    )
    (net (code "74") (name "unconnected-(U1-DIO_26-Pad39)") (class "Default")
      (node (ref "U1") (pin "39") (pinfunction "DIO_26_39") (pintype "bidirectional+no_connect"))
    )
    (net (code "75") (name "unconnected-(U1-DIO_27-Pad40)") (class "Default")
      (node (ref "U1") (pin "40") (pinfunction "DIO_27_40") (pintype "bidirectional+no_connect"))
    )
    (net (code "76") (name "unconnected-(U1-DIO_28-Pad41)") (class "Default")
      (node (ref "U1") (pin "41") (pinfunction "DIO_28_41") (pintype "bidirectional+no_connect"))
    )
    (net (code "77") (name "unconnected-(U1-DIO_29-Pad42)") (class "Default")
      (node (ref "U1") (pin "42") (pinfunction "DIO_29_42") (pintype "bidirectional+no_connect"))
    )
    (net (code "78") (name "unconnected-(U1-DIO_30-Pad43)") (class "Default")
      (node (ref "U1") (pin "43") (pinfunction "DIO_30_43") (pintype "bidirectional+no_connect"))
    )
    (net (code "79") (name "unconnected-(U4-PG-Pad2)") (class "Default")
      (node (ref "U4") (pin "2") (pinfunction "PG_2") (pintype "passive"))
    )
    (net (code "80") (name "unconnected-(U5-PIO0_2{slash}SSEL0{slash}CT16B0_CAP0-Pad8)") (class "Default")
      (node (ref "U5") (pin "8") (pinfunction "PIO0_2/SSEL0/CT16B0_CAP0_8") (pintype "passive"))
    )
    (net (code "81") (name "unconnected-(U5-PIO0_4{slash}SCL-Pad10)") (class "Default")
      (node (ref "U5") (pin "10") (pinfunction "PIO0_4/SCL_10") (pintype "passive"))
    )
    (net (code "82") (name "unconnected-(U5-PIO0_5{slash}SDA-Pad11)") (class "Default")
      (node (ref "U5") (pin "11") (pinfunction "PIO0_5/SDA_11") (pintype "passive"))
    )
    (net (code "83") (name "unconnected-(U5-PIO0_8{slash}MISO0{slash}CT16B0_MAT0-Pad17)") (class "Default")
      (node (ref "U5") (pin "17") (pinfunction "PIO0_8/MISO0/CT16B0_MAT0_17") (pintype "passive"))
    )
    (net (code "84") (name "unconnected-(U5-PIO0_9{slash}MOSI0{slash}CT16B0_MAT1{slash}SWO-Pad18)") (class "Default")
      (node (ref "U5") (pin "18") (pinfunction "PIO0_9/MOSI0/CT16B0_MAT1/SWO_18") (pintype "passive"))
    )
    (net (code "85") (name "unconnected-(U5-PIO0_16{slash}AD5{slash}CT32B1_MAT3{slash}WAKEUP-Pad26)") (class "Default")
      (node (ref "U5") (pin "26") (pinfunction "PIO0_16/AD5/CT32B1_MAT3/WAKEUP_26") (pintype "passive"))
    )
    (net (code "86") (name "unconnected-(U5-PIO0_17{slash}~{RTS}{slash}CT32B0_CAP0{slash}SCLK-Pad30)") (class "Default")
      (node (ref "U5") (pin "30") (pinfunction "PIO0_17/~{RTS}/CT32B0_CAP0/SCLK_30") (pintype "passive"))
    )
    (net (code "87") (name "unconnected-(U5-PIO0_18{slash}RXD{slash}CT32B0_MAT0-Pad31)") (class "Default")
      (node (ref "U5") (pin "31") (pinfunction "PIO0_18/RXD/CT32B0_MAT0_31") (pintype "passive"))
    )
    (net (code "88") (name "unconnected-(U5-PIO0_19{slash}TXD{slash}CT32B0_MAT1-Pad32)") (class "Default")
      (node (ref "U5") (pin "32") (pinfunction "PIO0_19/TXD/CT32B0_MAT1_32") (pintype "passive"))
    )
    (net (code "89") (name "unconnected-(U5-PIO0_20{slash}CT16B1_CAP0-Pad7)") (class "Default")
      (node (ref "U5") (pin "7") (pinfunction "PIO0_20/CT16B1_CAP0_7") (pintype "passive"))
    )
    (net (code "90") (name "unconnected-(U5-PIO0_23{slash}AD7-Pad27)") (class "Default")
      (node (ref "U5") (pin "27") (pinfunction "PIO0_23/AD7_27") (pintype "passive"))
    )
    (net (code "91") (name "unconnected-(U5-SWCLK{slash}PIO0_10{slash}SCK0{slash}CT16B0_MAT2-Pad19)") (class "Default")
      (node (ref "U5") (pin "19") (pinfunction "SWCLK/PIO0_10/SCK0/CT16B0_MAT2_19") (pintype "passive"))
    )
    (net (code "92") (name "unconnected-(U5-SWDIO{slash}PIO0_15{slash}AD4{slash}CT32B1_MAT2-Pad25)") (class "Default")
      (node (ref "U5") (pin "25") (pinfunction "SWDIO/PIO0_15/AD4/CT32B1_MAT2_25") (pintype "passive"))
    )
    (net (code "93") (name "unconnected-(U5-TDI{slash}PIO0_11{slash}AD0{slash}CT32B0_MAT3-Pad21)") (class "Default")
      (node (ref "U5") (pin "21") (pinfunction "TDI/PIO0_11/AD0/CT32B0_MAT3_21") (pintype "passive"))
    )
    (net (code "94") (name "unconnected-(U5-TDO{slash}PIO0_13{slash}AD2{slash}CT32B1_MAT0-Pad23)") (class "Default")
      (node (ref "U5") (pin "23") (pinfunction "TDO/PIO0_13/AD2/CT32B1_MAT0_23") (pintype "passive"))
    )
    (net (code "95") (name "unconnected-(U5-TMS{slash}PIO0_12{slash}AD1{slash}CT32B1_CAP0-Pad22)") (class "Default")
      (node (ref "U5") (pin "22") (pinfunction "TMS/PIO0_12/AD1/CT32B1_CAP0_22") (pintype "passive"))
    )
    (net (code "96") (name "unconnected-(U5-~{TRST}{slash}PIO0_14{slash}AD3{slash}CT32B1_MAT1-Pad24)") (class "Default")
      (node (ref "U5") (pin "24") (pinfunction "~{TRST}/PIO0_14/AD3/CT32B1_MAT1_24") (pintype "passive"))
    )
  )
)
